# POWER_SCHEM_REV2.net
KiCad netlist of a schematic drawn in Altium Designer
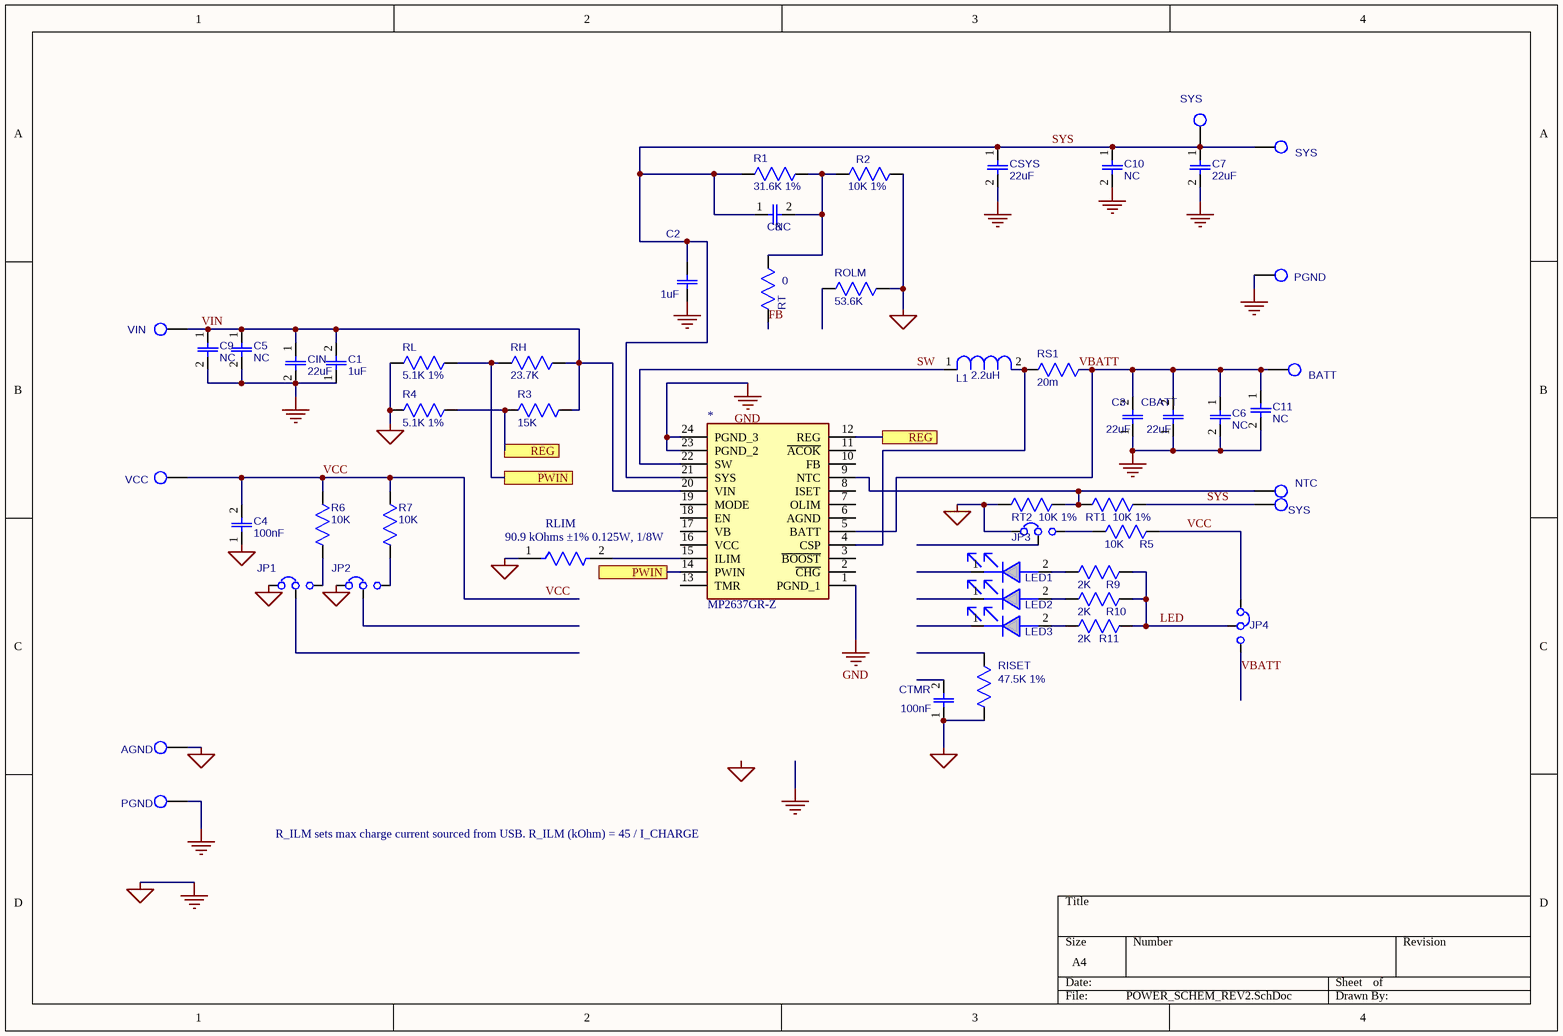
[diagram p0: POWER_SCHEM_REV2.SchDoc]

(export (version "E")
  (design (tool "Eeschema 10.0.6"))
  (components
    (comp (ref "*")
      (value "MP2637GR-Z")
      (footprint "SamacSys:MP2637GRZ")
      (description "Integrated Circuit")
      (fields (field (name "MOUSER PART NUMBER") "946-MP2637GR-Z"))
      (libsource (lib "*") (part "MP2637GR-Z"))
    )
    (comp (ref "C1")
      (value "1uF")
      (footprint "CAP/0603")
      (description "Ceramic Capacitor;25V;X7R")
      (fields (field (name "MANUFACTURER") "{Manufacturer}") (field (name "PART NUMBER") "07.0772"))
      (libsource (lib "MPSLab") (part "CAP/0603"))
    )
    (comp (ref "C2")
      (value "1uF")
      (footprint "CAP/0603")
      (description "Ceramic Capacitor;16V;X7R;0603;")
      (fields (field (name "MANUFACTURER") "{Manufacturer}") (field (name "PART NUMBER") "07.0043"))
      (libsource (lib "") (part "CAP/0603_1"))
    )
    (comp (ref "C3")
      (value "22uF")
      (footprint "CAP/1206")
      (description "Ceramic Capacitor;10V;X7R;1206")
      (fields (field (name "MANUFACTURER") "{Manufacturer}") (field (name "PART NUMBER") "07.0581"))
      (libsource (lib "MPSLab") (part "CAP/1206"))
    )
    (comp (ref "C4")
      (value "100nF")
      (footprint "CAP/0603")
      (description "Ceramic Capacitor;16V;X7R;0603;")
      (fields (field (name "MANUFACTURER") "{Manufacturer}") (field (name "PART NUMBER") "07.0053"))
      (libsource (lib "MPSLab") (part "CAP/0603"))
    )
    (comp (ref "C5")
      (value "NC")
      (footprint "CAP/1206")
      (description "Ceramic Capacitor;25V;X5R;")
      (fields (field (name "MANUFACTURER") "{Manufacturer}") (field (name "PART NUMBER") "07.0752"))
      (libsource (lib "MPSLab") (part "CAP/1206"))
    )
    (comp (ref "C6")
      (value "NC")
      (footprint "CAP/1206")
      (description "Ceramic Capacitor;10V;X7R;1206")
      (fields (field (name "MANUFACTURER") "{Manufacturer}") (field (name "PART NUMBER") "07.0581"))
      (libsource (lib "MPSLab") (part "CAP/1206"))
    )
    (comp (ref "C7")
      (value "22uF")
      (footprint "CAP/1206")
      (description "Ceramic Capacitor;10V;X7R;1206")
      (fields (field (name "MANUFACTURER") "{Manufacturer}") (field (name "PART NUMBER") "07.0581"))
      (libsource (lib "MPSLab") (part "CAP/1206"))
    )
    (comp (ref "C8")
      (value "NC")
      (footprint "CAP/0603")
      (description "Ceramic Capacitor;50V;C0G;0603;")
      (fields (field (name "MANUFACTURER") "{Manufacturer}") (field (name "PART NUMBER") "07.0138"))
      (libsource (lib "MPSLab") (part "CAP/0603"))
    )
    (comp (ref "C9")
      (value "NC")
      (footprint "CAP/0603")
      (description "Ceramic Capacitor;25V;X7R")
      (fields (field (name "MANUFACTURER") "{Manufacturer}") (field (name "PART NUMBER") "07.0772"))
      (libsource (lib "MPSLab") (part "CAP/0603"))
    )
    (comp (ref "C10")
      (value "NC")
      (footprint "CAP/0603")
      (description "Ceramic Capacitor;16V;X7R;0603;")
      (fields (field (name "MANUFACTURER") "{Manufacturer}") (field (name "PART NUMBER") "07.0043"))
      (libsource (lib "MPSLab") (part "CAP/0603"))
    )
    (comp (ref "C11")
      (value "NC")
      (footprint "CAP/0603")
      (description "Ceramic Capacitor;16V;X7R;0603;")
      (fields (field (name "MANUFACTURER") "{Manufacturer}") (field (name "PART NUMBER") "07.0043"))
      (libsource (lib "MPSLab") (part "CAP/0603"))
    )
    (comp (ref "CBATT")
      (value "22uF")
      (footprint "CAP/1206")
      (description "Ceramic Capacitor;10V;X7R;1206")
      (fields (field (name "MANUFACTURER") "{Manufacturer}") (field (name "PART NUMBER") "07.0581"))
      (libsource (lib "MPSLab") (part "CAP/1206"))
    )
    (comp (ref "CIN")
      (value "22uF")
      (footprint "CAP/1206")
      (description "Ceramic Capacitor;25V;X5R;")
      (fields (field (name "MANUFACTURER") "{Manufacturer}") (field (name "PART NUMBER") "07.0752"))
      (libsource (lib "MPSLab") (part "CAP/1206"))
    )
    (comp (ref "CSYS")
      (value "22uF")
      (footprint "CAP/1206")
      (description "Ceramic Capacitor;10V;X7R;1206")
      (fields (field (name "MANUFACTURER") "{Manufacturer}") (field (name "PART NUMBER") "07.0581"))
      (libsource (lib "MPSLab") (part "CAP/1206"))
    )
    (comp (ref "CTMR")
      (value "100nF")
      (footprint "CAP/0603")
      (description "Ceramic Capacitor;50V;X7R;0603;")
      (fields (field (name "MANUFACTURER") "{Manufacturer}") (field (name "PART NUMBER") "07.0051"))
      (libsource (lib "MPSLab") (part "CAP/0603"))
    )
    (comp (ref "JP1")
      (value "JUMPER/3PIN/DIP/2.54MM/B")
      (footprint "JUMPER/3P/DIP/2.54MM")
      (description "{Description}")
      (fields (field (name "MANUFACTURER") "{Manufacturer}"))
      (libsource (lib "Jumper") (part "JUMPER/3PIN/DIP/2.54MM/B"))
    )
    (comp (ref "JP2")
      (value "JUMPER/3PIN/DIP/2.54MM/B")
      (footprint "JUMPER/3P/DIP/2.54MM")
      (description "{Description}")
      (fields (field (name "MANUFACTURER") "{Manufacturer}"))
      (libsource (lib "Jumper") (part "JUMPER/3PIN/DIP/2.54MM/B"))
    )
    (comp (ref "JP3")
      (value "JUMPER/3PIN/DIP/2.54MM/B")
      (footprint "JUMPER/3P/DIP/2.54MM")
      (description "{Description}")
      (fields (field (name "MANUFACTURER") "{Manufacturer}"))
      (libsource (lib "Jumper") (part "JUMPER/3PIN/DIP/2.54MM/B"))
    )
    (comp (ref "JP4")
      (value "JUMPER/3PIN/DIP/2.54MM/B")
      (footprint "JUMPER/3P/DIP/2.54MM")
      (description "{Description}")
      (fields (field (name "MANUFACTURER") "{Manufacturer}"))
      (libsource (lib "") (part "JUMPER/3PIN/DIP/2.54MM/B_1"))
    )
    (comp (ref "L1")
      (value "2.2uH")
      (footprint "IND/Murata/LQH88PN")
      (description "Inductor;2.2uH;9m;7.2A")
      (fields (field (name "MANUFACTURER") "{Manufacturer}") (field (name "PART NUMBER") "03.0311"))
      (libsource (lib "MPSLab") (part "INDUCTOR"))
    )
    (comp (ref "LED1")
      (value "LED/SMD/0805")
      (footprint "LED/SMD/0805")
      (description "LED;红光;")
      (fields (field (name "MANUFACTURER") "{Manufacturer}") (field (name "PART NUMBER") "19.0003"))
      (libsource (lib "MPSLab") (part "LED/SMD/0805"))
    )
    (comp (ref "LED2")
      (value "LED/SMD/0805")
      (footprint "LED/SMD/0805")
      (description "LED;红光;")
      (fields (field (name "MANUFACTURER") "{Manufacturer}") (field (name "PART NUMBER") "19.0003"))
      (libsource (lib "MPSLab") (part "LED/SMD/0805"))
    )
    (comp (ref "LED3")
      (value "LED/SMD/0805")
      (footprint "LED/SMD/0805")
      (description "LED;红光;")
      (fields (field (name "MANUFACTURER") "{Manufacturer}") (field (name "PART NUMBER") "19.0003"))
      (libsource (lib "MPSLab") (part "LED/SMD/0805"))
    )
    (comp (ref "R1")
      (value "31.6K 1%")
      (footprint "RES/0603")
      (description "Film Resistor;1%;")
      (fields (field (name "MANUFACTURER") "Yageo") (field (name "PART NUMBER") "06.0160"))
      (libsource (lib "MPSLab") (part "RES/0603"))
    )
    (comp (ref "R2")
      (value "10K 1%")
      (footprint "RES/0603")
      (description "Film Resistor;1%;")
      (fields (field (name "MANUFACTURER") "Yageo") (field (name "PART NUMBER") "06.0112"))
      (libsource (lib "MPSLab") (part "RES/0603"))
    )
    (comp (ref "R3")
      (value "15K")
      (footprint "RES/0603")
      (description "Film Resistor;1%;")
      (fields (field (name "MANUFACTURER") "Yageo") (field (name "PART NUMBER") "06.0129"))
      (libsource (lib "MPSLab") (part "RES/0603"))
    )
    (comp (ref "R4")
      (value "5.1K 1%")
      (footprint "RES/0603")
      (description "Film Resistor;1%;")
      (fields (field (name "MANUFACTURER") "Yageo") (field (name "PART NUMBER") "06.0691"))
      (libsource (lib "MPSLab") (part "RES/0603"))
    )
    (comp (ref "R5")
      (value "10K")
      (footprint "RES/0603")
      (description "Film Resistor;5%;")
      (fields (field (name "MANUFACTURER") "Yageo") (field (name "PART NUMBER") "06.0284"))
      (libsource (lib "MPSLab") (part "RES/0603"))
    )
    (comp (ref "R6")
      (value "10K")
      (footprint "RES/0603")
      (description "Film Resistor;5%;")
      (fields (field (name "MANUFACTURER") "Yageo") (field (name "PART NUMBER") "06.0284"))
      (libsource (lib "MPSLab") (part "RES/0603"))
    )
    (comp (ref "R7")
      (value "10K")
      (footprint "RES/0603")
      (description "Film Resistor;5%;")
      (fields (field (name "MANUFACTURER") "Yageo") (field (name "PART NUMBER") "06.0284"))
      (libsource (lib "MPSLab") (part "RES/0603"))
    )
    (comp (ref "R9")
      (value "2K")
      (footprint "RES/0603")
      (description "Film Resistor;5%;1/10W")
      (fields (field (name "MANUFACTURER") "Yageo") (field (name "PART NUMBER") "06.0015"))
      (libsource (lib "MPSLab") (part "RES/0603"))
    )
    (comp (ref "R10")
      (value "2K")
      (footprint "RES/0603")
      (description "Film Resistor;5%;1/10W")
      (fields (field (name "MANUFACTURER") "Yageo") (field (name "PART NUMBER") "06.0015"))
      (libsource (lib "MPSLab") (part "RES/0603"))
    )
    (comp (ref "R11")
      (value "2K")
      (footprint "RES/0603")
      (description "Film Resistor;5%;1/10W")
      (fields (field (name "MANUFACTURER") "Yageo") (field (name "PART NUMBER") "06.0015"))
      (libsource (lib "MPSLab") (part "RES/0603"))
    )
    (comp (ref "RH")
      (value "23.7K")
      (footprint "RES/0603")
      (description "Film Resistor;1%")
      (fields (field (name "MANUFACTURER") "Yageo") (field (name "PART NUMBER") "06.0148"))
      (libsource (lib "MPSLab") (part "RES/0603"))
    )
    (comp (ref "RISET")
      (value "47.5K 1%")
      (footprint "RES/0603")
      (description "Film Resistor;1%")
      (fields (field (name "MANUFACTURER") "Yageo") (field (name "PART NUMBER") "06.0177"))
      (libsource (lib "MPSLab") (part "RES/0603"))
    )
    (comp (ref "RL")
      (value "5.1K 1%")
      (footprint "RES/0603")
      (description "Film Resistor;1%;")
      (fields (field (name "MANUFACTURER") "Yageo") (field (name "PART NUMBER") "06.0691"))
      (libsource (lib "MPSLab") (part "RES/0603"))
    )
    (comp (ref "RLIM")
      (value "90.9 kOhms ±1% 0.125W, 1/8W")
      (footprint "FP-MCT0603-MFG")
      (fields (field (name "TOLERANCE") "1%"))
      (libsource (lib "Altium Content Vault") (part "1029c3af85768c4190bb7ad29bc67b5"))
    )
    (comp (ref "ROLM")
      (value "53.6K")
      (footprint "RES/0603")
      (description "Film Resistor;1%")
      (fields (field (name "MANUFACTURER") "Yageo") (field (name "PART NUMBER") "06.0182"))
      (libsource (lib "MPSLab") (part "RES/0603"))
    )
    (comp (ref "RS1")
      (value "20m")
      (footprint "RES/1206")
      (description "Film Resistor;1%")
      (fields (field (name "MANUFACTURER") "Yageo") (field (name "PART NUMBER") "06.0564"))
      (libsource (lib "MPSLab") (part "RES/1206"))
    )
    (comp (ref "RT")
      (value "0")
      (footprint "RES/0603")
      (description "Film Resistor;5%;")
      (fields (field (name "MANUFACTURER") "Yageo") (field (name "PART NUMBER") "06.0039"))
      (libsource (lib "MPSLab") (part "RES/0603"))
    )
    (comp (ref "RT1")
      (value "10K 1%")
      (footprint "RES/0603")
      (description "Film Resistor;1%;")
      (fields (field (name "MANUFACTURER") "Yageo") (field (name "PART NUMBER") "06.0112"))
      (libsource (lib "MPSLab") (part "RES/0603"))
    )
    (comp (ref "RT2")
      (value "10K 1%")
      (footprint "RES/0603")
      (description "Film Resistor;1%;")
      (fields (field (name "MANUFACTURER") "Yageo") (field (name "PART NUMBER") "06.0112"))
      (libsource (lib "MPSLab") (part "RES/0603"))
    )
    (comp (ref "TP1")
      (value "VIN")
      (footprint "CONN/2MM")
      (description "Connector;")
      (fields (field (name "MANUFACTURER") "{Manufacturer}") (field (name "PART NUMBER") "17.0025"))
      (libsource (lib "MPSLab") (part "CONN/TP"))
    )
    (comp (ref "TP2")
      (value "PGND")
      (footprint "CONN/2MM")
      (description "Connector;")
      (fields (field (name "MANUFACTURER") "{Manufacturer}") (field (name "PART NUMBER") "17.0025"))
      (libsource (lib "MPSLab") (part "CONN/TP"))
    )
    (comp (ref "TP3")
      (value "VCC")
      (footprint "CONN/1MM")
      (description "Connector;")
      (fields (field (name "MANUFACTURER") "{Manufacturer}") (field (name "PART NUMBER") "17.0025"))
      (libsource (lib "MPSLab") (part "CONN/TP"))
    )
    (comp (ref "TP5")
      (value "AGND")
      (footprint "CONN/1MM")
      (description "Connector;")
      (fields (field (name "MANUFACTURER") "{Manufacturer}") (field (name "PART NUMBER") "17.0025"))
      (libsource (lib "MPSLab") (part "CONN/TP"))
    )
    (comp (ref "TP6")
      (value "SYS")
      (footprint "CONN/2MM")
      (description "Connector;")
      (fields (field (name "MANUFACTURER") "{Manufacturer}") (field (name "PART NUMBER") "17.0025"))
      (libsource (lib "MPSLab") (part "CONN/TP"))
    )
    (comp (ref "TP8")
      (value "SYS")
      (footprint "CONN/1MM")
      (description "Connector;")
      (fields (field (name "MANUFACTURER") "{Manufacturer}") (field (name "PART NUMBER") "17.0025"))
      (libsource (lib "MPSLab") (part "CONN/TP"))
    )
    (comp (ref "TP9")
      (value "BATT")
      (footprint "CONN/2MM")
      (description "Connector;")
      (fields (field (name "MANUFACTURER") "{Manufacturer}") (field (name "PART NUMBER") "17.0025"))
      (libsource (lib "MPSLab") (part "CONN/TP"))
    )
    (comp (ref "TP10")
      (value "NTC")
      (footprint "CONN/1MM")
      (description "Connector;")
      (fields (field (name "MANUFACTURER") "{Manufacturer}") (field (name "PART NUMBER") "17.0025"))
      (libsource (lib "MPSLab") (part "CONN/TP"))
    )
    (comp (ref "TP11")
      (value "PGND")
      (footprint "CONN/2MM")
      (description "Connector;")
      (fields (field (name "MANUFACTURER") "{Manufacturer}") (field (name "PART NUMBER") "17.0025"))
      (libsource (lib "MPSLab") (part "CONN/TP"))
    )
    (comp (ref "TP12")
      (value "SYS")
      (footprint "CONN/1MM")
      (description "Connector;")
      (fields (field (name "MANUFACTURER") "{Manufacturer}") (field (name "PART NUMBER") "17.0025"))
      (libsource (lib "MPSLab") (part "CONN/TP"))
    )
  )
  (nets
    (net (code "1") (name "/FB") (class "Default") (node (ref "RT") (pin "2") (pintype "passive")))
    (net (code "2") (name "/LED") (class "Default")
      (node (ref "JP4") (pin "2") (pinfunction "2_2") (pintype "passive"))
      (node (ref "R10") (pin "1") (pintype "passive"))
      (node (ref "R11") (pin "1") (pintype "passive"))
      (node (ref "R9") (pin "1") (pintype "passive"))
    )
    (net (code "3") (name "/PWIN") (class "Default")
      (node (ref "*") (pin "14") (pinfunction "PWIN_14") (pintype "passive"))
      (node (ref "RH") (pin "1") (pintype "passive"))
      (node (ref "RL") (pin "2") (pintype "passive"))
    )
    (net (code "4") (name "/REG") (class "Default")
      (node (ref "*") (pin "12") (pinfunction "REG_12") (pintype "passive"))
      (node (ref "R3") (pin "1") (pintype "passive"))
      (node (ref "R4") (pin "2") (pintype "passive"))
    )
    (net (code "5") (name "/SW") (class "Default")
      (node (ref "*") (pin "22") (pinfunction "SW_22") (pintype "passive"))
      (node (ref "L1") (pin "1") (pintype "passive"))
    )
    (net (code "6") (name "/SYS") (class "Default")
      (node (ref "*") (pin "21") (pinfunction "SYS_21") (pintype "passive"))
      (node (ref "C10") (pin "1") (pintype "passive"))
      (node (ref "C2") (pin "2") (pintype "passive"))
      (node (ref "C7") (pin "1") (pintype "passive"))
      (node (ref "C8") (pin "1") (pintype "passive"))
      (node (ref "CSYS") (pin "1") (pintype "passive"))
      (node (ref "R1") (pin "2") (pintype "passive"))
      (node (ref "RT1") (pin "1") (pintype "passive"))
      (node (ref "TP12") (pin "1") (pintype "passive"))
      (node (ref "TP6") (pin "1") (pintype "passive"))
      (node (ref "TP8") (pin "1") (pintype "passive"))
    )
    (net (code "7") (name "/VBATT") (class "Default")
      (node (ref "*") (pin "5") (pinfunction "BATT_5") (pintype "passive"))
      (node (ref "C11") (pin "1") (pintype "passive"))
      (node (ref "C3") (pin "2") (pintype "passive"))
      (node (ref "C6") (pin "1") (pintype "passive"))
      (node (ref "CBATT") (pin "2") (pintype "passive"))
      (node (ref "JP4") (pin "3") (pinfunction "3_3") (pintype "passive"))
      (node (ref "RS1") (pin "1") (pintype "passive"))
      (node (ref "TP9") (pin "1") (pintype "passive"))
    )
    (net (code "8") (name "/VCC") (class "Default")
      (node (ref "C4") (pin "2") (pintype "passive"))
      (node (ref "JP4") (pin "1") (pinfunction "1_1") (pintype "passive"))
      (node (ref "R5") (pin "2") (pintype "passive"))
      (node (ref "R6") (pin "2") (pintype "passive"))
      (node (ref "R7") (pin "2") (pintype "passive"))
      (node (ref "TP3") (pin "1") (pintype "passive"))
    )
    (net (code "9") (name "/VIN") (class "Default")
      (node (ref "*") (pin "20") (pinfunction "VIN_20") (pintype "passive"))
      (node (ref "C1") (pin "2") (pintype "passive"))
      (node (ref "C5") (pin "1") (pintype "passive"))
      (node (ref "C9") (pin "1") (pintype "passive"))
      (node (ref "CIN") (pin "1") (pintype "passive"))
      (node (ref "R3") (pin "2") (pintype "passive"))
      (node (ref "RH") (pin "2") (pintype "passive"))
      (node (ref "TP1") (pin "1") (pintype "passive"))
    )
    (net (code "10") (name "GND") (class "Default")
      (node (ref "*") (pin "1") (pinfunction "PGND_1_1") (pintype "passive"))
      (node (ref "*") (pin "23") (pinfunction "PGND_2_23") (pintype "passive"))
      (node (ref "*") (pin "24") (pinfunction "PGND_3_24") (pintype "passive"))
      (node (ref "C1") (pin "1") (pintype "passive"))
      (node (ref "C10") (pin "2") (pintype "passive"))
      (node (ref "C11") (pin "2") (pintype "passive"))
      (node (ref "C2") (pin "1") (pintype "passive"))
      (node (ref "C3") (pin "1") (pintype "passive"))
      (node (ref "C4") (pin "1") (pintype "passive"))
      (node (ref "C5") (pin "2") (pintype "passive"))
      (node (ref "C6") (pin "2") (pintype "passive"))
      (node (ref "C7") (pin "2") (pintype "passive"))
      (node (ref "C9") (pin "2") (pintype "passive"))
      (node (ref "CBATT") (pin "1") (pintype "passive"))
      (node (ref "CIN") (pin "2") (pintype "passive"))
      (node (ref "CSYS") (pin "2") (pintype "passive"))
      (node (ref "CTMR") (pin "1") (pintype "passive"))
      (node (ref "JP1") (pin "1") (pinfunction "1_1") (pintype "passive"))
      (node (ref "JP2") (pin "1") (pinfunction "1_1") (pintype "passive"))
      (node (ref "JP3") (pin "1") (pinfunction "1_1") (pintype "passive"))
      (node (ref "R2") (pin "1") (pintype "passive"))
      (node (ref "R4") (pin "1") (pintype "passive"))
      (node (ref "RISET") (pin "1") (pintype "passive"))
      (node (ref "RL") (pin "1") (pintype "passive"))
      (node (ref "RLIM") (pin "1") (pinfunction "1_1") (pintype "passive"))
      (node (ref "ROLM") (pin "1") (pintype "passive"))
      (node (ref "RT2") (pin "2") (pintype "passive"))
      (node (ref "TP11") (pin "1") (pintype "passive"))
      (node (ref "TP2") (pin "1") (pintype "passive"))
      (node (ref "TP5") (pin "1") (pintype "passive"))
    )
    (net (code "11") (name "Net-(*-CSP)") (class "Default")
      (node (ref "*") (pin "4") (pinfunction "CSP_4") (pintype "passive"))
      (node (ref "L1") (pin "2") (pintype "passive"))
      (node (ref "RS1") (pin "2") (pintype "passive"))
    )
    (net (code "12") (name "Net-(*-ILIM)") (class "Default")
      (node (ref "*") (pin "15") (pinfunction "ILIM_15") (pintype "passive"))
      (node (ref "RLIM") (pin "2") (pinfunction "2_2") (pintype "passive"))
    )
    (net (code "13") (name "Net-(*-NTC)") (class "Default")
      (node (ref "*") (pin "9") (pinfunction "NTC_9") (pintype "passive"))
      (node (ref "RT1") (pin "2") (pintype "passive"))
      (node (ref "RT2") (pin "1") (pintype "passive"))
      (node (ref "TP10") (pin "1") (pintype "passive"))
    )
    (net (code "14") (name "Net-(C8-Pad2)") (class "Default")
      (node (ref "C8") (pin "2") (pintype "passive"))
      (node (ref "R1") (pin "1") (pintype "passive"))
      (node (ref "R2") (pin "2") (pintype "passive"))
      (node (ref "RT") (pin "1") (pintype "passive"))
    )
    (net (code "15") (name "Net-(JP1-Pad3)") (class "Default")
      (node (ref "JP1") (pin "3") (pinfunction "3_3") (pintype "passive"))
      (node (ref "R6") (pin "1") (pintype "passive"))
    )
    (net (code "16") (name "Net-(JP2-Pad3)") (class "Default")
      (node (ref "JP2") (pin "3") (pinfunction "3_3") (pintype "passive"))
      (node (ref "R7") (pin "1") (pintype "passive"))
    )
    (net (code "17") (name "Net-(JP3-Pad3)") (class "Default")
      (node (ref "JP3") (pin "3") (pinfunction "3_3") (pintype "passive"))
      (node (ref "R5") (pin "1") (pintype "passive"))
    )
    (net (code "18") (name "Net-(LED1-Pad2)") (class "Default")
      (node (ref "LED1") (pin "2") (pintype "passive"))
      (node (ref "R9") (pin "2") (pintype "passive"))
    )
    (net (code "19") (name "Net-(LED2-Pad2)") (class "Default")
      (node (ref "LED2") (pin "2") (pintype "passive"))
      (node (ref "R10") (pin "2") (pintype "passive"))
    )
    (net (code "20") (name "Net-(LED3-Pad2)") (class "Default")
      (node (ref "LED3") (pin "2") (pintype "passive"))
      (node (ref "R11") (pin "2") (pintype "passive"))
    )
    (net (code "21") (name "unconnected-(*-AGND-Pad6)") (class "Default")
      (node (ref "*") (pin "6") (pinfunction "AGND_6") (pintype "passive"))
    )
    (net (code "22") (name "unconnected-(*-EN-Pad18)") (class "Default")
      (node (ref "*") (pin "18") (pinfunction "EN_18") (pintype "passive"))
    )
    (net (code "23") (name "unconnected-(*-FB-Pad10)") (class "Default")
      (node (ref "*") (pin "10") (pinfunction "FB_10") (pintype "passive"))
    )
    (net (code "24") (name "unconnected-(*-ISET-Pad8)") (class "Default")
      (node (ref "*") (pin "8") (pinfunction "ISET_8") (pintype "passive"))
    )
    (net (code "25") (name "unconnected-(*-MODE-Pad19)") (class "Default")
      (node (ref "*") (pin "19") (pinfunction "MODE_19") (pintype "passive"))
    )
    (net (code "26") (name "unconnected-(*-OLIM-Pad7)") (class "Default")
      (node (ref "*") (pin "7") (pinfunction "OLIM_7") (pintype "passive"))
    )
    (net (code "27") (name "unconnected-(*-TMR-Pad13)") (class "Default")
      (node (ref "*") (pin "13") (pinfunction "TMR_13") (pintype "passive"))
    )
    (net (code "28") (name "unconnected-(*-VB-Pad17)") (class "Default")
      (node (ref "*") (pin "17") (pinfunction "VB_17") (pintype "passive"))
    )
    (net (code "29") (name "unconnected-(*-VCC-Pad16)") (class "Default")
      (node (ref "*") (pin "16") (pinfunction "VCC_16") (pintype "passive"))
    )
    (net (code "30") (name "unconnected-(*-~{ACOK}-Pad11)") (class "Default")
      (node (ref "*") (pin "11") (pinfunction "~{ACOK}_11") (pintype "passive"))
    )
    (net (code "31") (name "unconnected-(*-~{BOOST}-Pad3)") (class "Default")
      (node (ref "*") (pin "3") (pinfunction "~{BOOST}_3") (pintype "passive"))
    )
    (net (code "32") (name "unconnected-(*-~{CHG}-Pad2)") (class "Default")
      (node (ref "*") (pin "2") (pinfunction "~{CHG}_2") (pintype "passive"))
    )
    (net (code "33") (name "unconnected-(CTMR-Pad2)") (class "Default")
      (node (ref "CTMR") (pin "2") (pintype "passive"))
    )
    (net (code "34") (name "unconnected-(JP1-Pad2)") (class "Default")
      (node (ref "JP1") (pin "2") (pinfunction "2_2") (pintype "passive"))
    )
    (net (code "35") (name "unconnected-(JP2-Pad2)") (class "Default")
      (node (ref "JP2") (pin "2") (pinfunction "2_2") (pintype "passive"))
    )
    (net (code "36") (name "unconnected-(JP3-Pad2)") (class "Default")
      (node (ref "JP3") (pin "2") (pinfunction "2_2") (pintype "passive"))
    )
    (net (code "37") (name "unconnected-(LED1-Pad1)") (class "Default")
      (node (ref "LED1") (pin "1") (pintype "passive"))
    )
    (net (code "38") (name "unconnected-(LED2-Pad1)") (class "Default")
      (node (ref "LED2") (pin "1") (pintype "passive"))
    )
    (net (code "39") (name "unconnected-(LED3-Pad1)") (class "Default")
      (node (ref "LED3") (pin "1") (pintype "passive"))
    )
    (net (code "40") (name "unconnected-(RISET-Pad2)") (class "Default")
      (node (ref "RISET") (pin "2") (pintype "passive"))
    )
    (net (code "41") (name "unconnected-(ROLM-Pad2)") (class "Default")
      (node (ref "ROLM") (pin "2") (pintype "passive"))
    )
  )
)
